# RS232_V2.net
KiCad netlist of a schematic drawn in Altium Designer
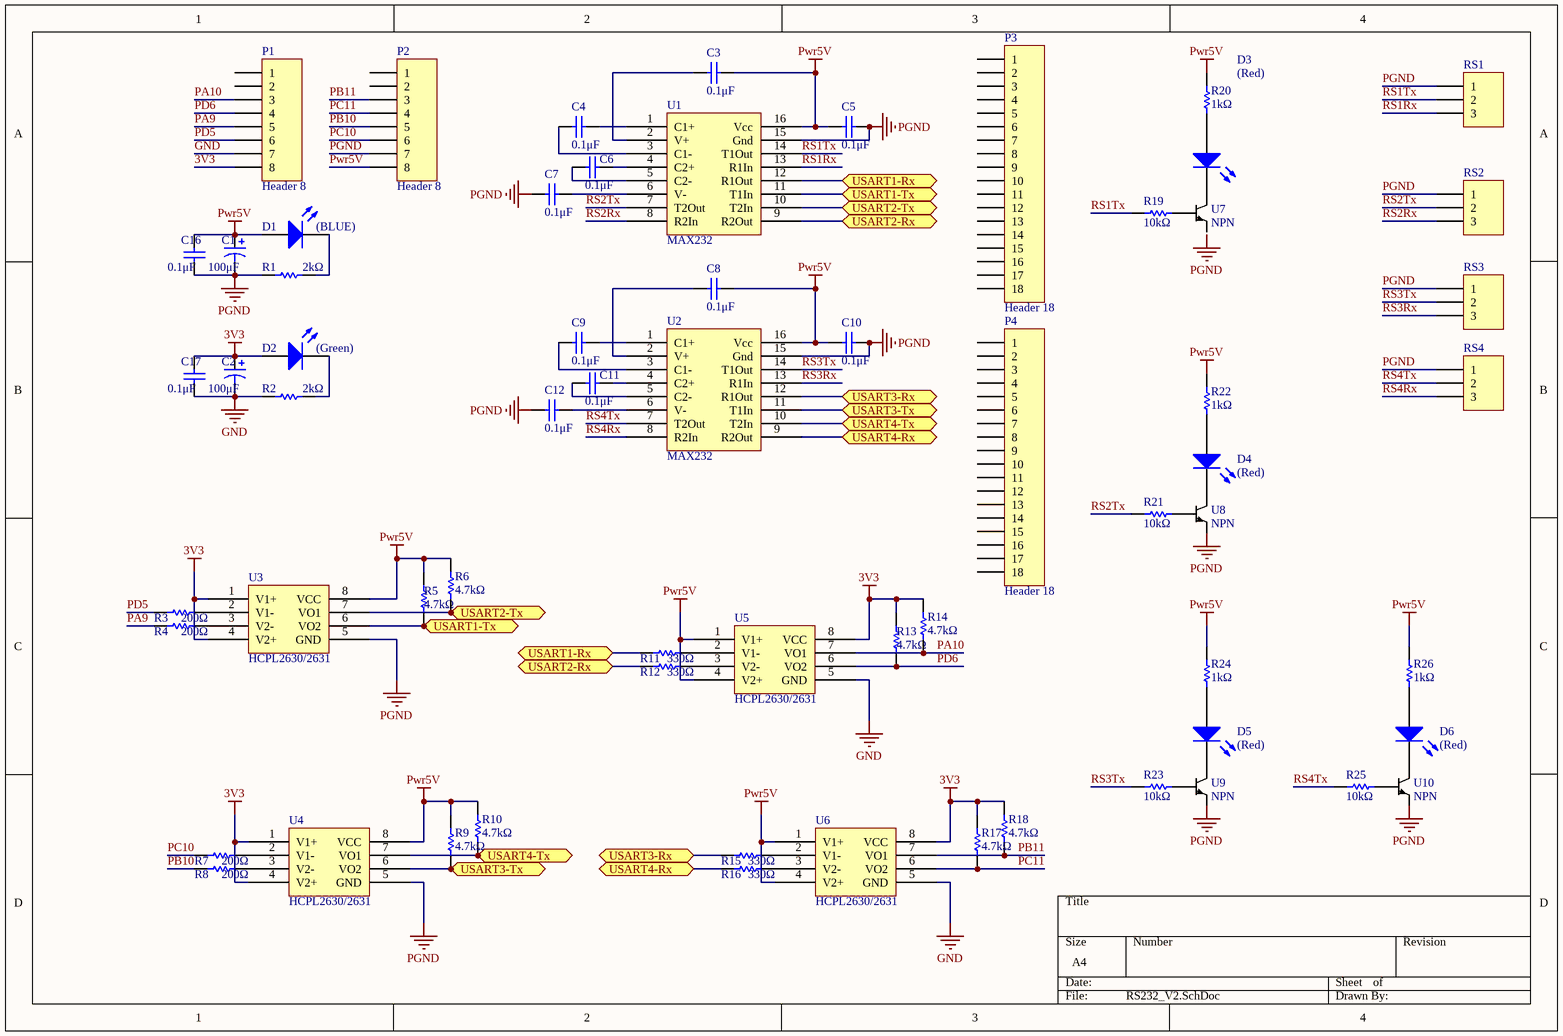
[diagram p0: RS232_V2.SchDoc]

(export (version "E")
  (design (tool "Eeschema 10.0.6"))
  (components
    (comp (ref "C1")
      (value "100μF")
      (footprint "CAP-TAN-6032/CAPC")
      (description "钽电容")
      (fields (field (name "Comment") "CAP-TAN") (field (name "PUBLISHER") "Altium Limited"))
      (libsource (lib "Libraries_2014_0215") (part "CAP-TAN"))
    )
    (comp (ref "C2")
      (value "100μF")
      (footprint "CAP-TAN-6032/CAPC")
      (description "钽电容")
      (fields (field (name "Comment") "CAP-TAN") (field (name "PUBLISHER") "Altium Limited"))
      (libsource (lib "Libraries_2014_0215") (part "CAP-TAN"))
    )
    (comp (ref "C3")
      (value "0.1μF")
      (footprint "CAP-MLCC-0603")
      (description "无极性电容")
      (fields (field (name "PUBLISHER") "Altium Limited"))
      (libsource (lib "Libraries_2014_0618") (part "CAP"))
    )
    (comp (ref "C4")
      (value "0.1μF")
      (footprint "CAP-MLCC-0603")
      (description "无极性电容")
      (fields (field (name "PUBLISHER") "Altium Limited"))
      (libsource (lib "Libraries_2014_0618") (part "CAP"))
    )
    (comp (ref "C5")
      (value "0.1μF")
      (footprint "CAP-MLCC-0603")
      (description "无极性电容")
      (fields (field (name "PUBLISHER") "Altium Limited"))
      (libsource (lib "Libraries_2014_0618") (part "CAP"))
    )
    (comp (ref "C6")
      (value "0.1μF")
      (footprint "CAP-MLCC-0603")
      (description "无极性电容")
      (fields (field (name "PUBLISHER") "Altium Limited"))
      (libsource (lib "Libraries_2014_0618") (part "CAP"))
    )
    (comp (ref "C7")
      (value "0.1μF")
      (footprint "CAP-MLCC-0603")
      (description "无极性电容")
      (fields (field (name "PUBLISHER") "Altium Limited"))
      (libsource (lib "Libraries_2014_0618") (part "CAP"))
    )
    (comp (ref "C8")
      (value "0.1μF")
      (footprint "CAP-MLCC-0603")
      (description "无极性电容")
      (fields (field (name "PUBLISHER") "Altium Limited"))
      (libsource (lib "Libraries_2014_0618") (part "CAP"))
    )
    (comp (ref "C9")
      (value "0.1μF")
      (footprint "CAP-MLCC-0603")
      (description "无极性电容")
      (fields (field (name "PUBLISHER") "Altium Limited"))
      (libsource (lib "Libraries_2014_0618") (part "CAP"))
    )
    (comp (ref "C10")
      (value "0.1μF")
      (footprint "CAP-MLCC-0603")
      (description "无极性电容")
      (fields (field (name "PUBLISHER") "Altium Limited"))
      (libsource (lib "Libraries_2014_0618") (part "CAP"))
    )
    (comp (ref "C11")
      (value "0.1μF")
      (footprint "CAP-MLCC-0603")
      (description "无极性电容")
      (fields (field (name "PUBLISHER") "Altium Limited"))
      (libsource (lib "Libraries_2014_0618") (part "CAP"))
    )
    (comp (ref "C12")
      (value "0.1μF")
      (footprint "CAP-MLCC-0603")
      (description "无极性电容")
      (fields (field (name "PUBLISHER") "Altium Limited"))
      (libsource (lib "Libraries_2014_0618") (part "CAP"))
    )
    (comp (ref "C16")
      (value "0.1μF")
      (footprint "CAP-MLCC-0603")
      (description "无极性电容")
      (fields (field (name "PUBLISHER") "Altium Limited"))
      (libsource (lib "Libraries_2014_0618") (part "CAP"))
    )
    (comp (ref "C17")
      (value "0.1μF")
      (footprint "CAP-MLCC-0603")
      (description "无极性电容")
      (fields (field (name "PUBLISHER") "Altium Limited"))
      (libsource (lib "Libraries_2014_0618") (part "CAP"))
    )
    (comp (ref "D1")
      (value "(BLUE)")
      (footprint "LED-0805")
      (description "LED")
      (fields (field (name "PUBLISHER") "Altium Limited"))
      (libsource (lib "Libraries_2014_0215") (part "LED"))
    )
    (comp (ref "D2")
      (value "(Green)")
      (footprint "LED-0805")
      (description "LED")
      (fields (field (name "PUBLISHER") "Altium Limited"))
      (libsource (lib "Libraries_2014_0215") (part "LED"))
    )
    (comp (ref "D3")
      (value "(Red)")
      (footprint "LED-0805")
      (description "LED")
      (fields (field (name "PUBLISHER") "Altium Limited"))
      (libsource (lib "Libraries_2014_0618") (part "LED"))
    )
    (comp (ref "D4")
      (value "(Red)")
      (footprint "LED-0805")
      (description "LED")
      (fields (field (name "PUBLISHER") "Altium Limited"))
      (libsource (lib "Libraries_2014_0618") (part "LED"))
    )
    (comp (ref "D5")
      (value "(Red)")
      (footprint "LED-0805")
      (description "LED")
      (fields (field (name "PUBLISHER") "Altium Limited"))
      (libsource (lib "Libraries_2014_0618") (part "LED"))
    )
    (comp (ref "D6")
      (value "(Red)")
      (footprint "LED-0805")
      (description "LED")
      (fields (field (name "PUBLISHER") "Altium Limited"))
      (libsource (lib "Libraries_2014_0618") (part "LED"))
    )
    (comp (ref "P1")
      (value "Header 8")
      (footprint "SIP8")
      (description "Header, 8-Pin")
      (fields (field (name "PUBLISHER") "Altium Limited"))
      (libsource (lib "Libraries_2014_0618") (part "Header 8"))
    )
    (comp (ref "P2")
      (value "Header 8")
      (footprint "SIP8")
      (description "Header, 8-Pin")
      (fields (field (name "PUBLISHER") "Altium Limited"))
      (libsource (lib "Libraries_2014_0618") (part "Header 8"))
    )
    (comp (ref "P3")
      (value "Header 18")
      (footprint "SIP18")
      (description "Header, 18-Pin")
      (fields (field (name "PUBLISHER") "Altium Limited"))
      (libsource (lib "Libraries_2014_0618") (part "Header 18"))
    )
    (comp (ref "P4")
      (value "Header 18")
      (footprint "SIP18")
      (description "Header, 18-Pin")
      (fields (field (name "PUBLISHER") "Altium Limited"))
      (libsource (lib "Libraries_2014_0618") (part "Header 18"))
    )
    (comp (ref "R1")
      (value "2kΩ")
      (footprint "RES-0603")
      (description "电阻")
      (fields (field (name "Comment") "RES") (field (name "PUBLISHER") "Altium Limited"))
      (libsource (lib "Libraries_2014_0215") (part "RES"))
    )
    (comp (ref "R2")
      (value "2kΩ")
      (footprint "RES-0603")
      (description "电阻")
      (fields (field (name "Comment") "RES") (field (name "PUBLISHER") "Altium Limited"))
      (libsource (lib "Libraries_2014_0215") (part "RES"))
    )
    (comp (ref "R3")
      (value "200Ω")
      (footprint "RES-0603")
      (description "电阻")
      (fields (field (name "PUBLISHER") "Altium Limited"))
      (libsource (lib "Libraries_2014_0618") (part "RES"))
    )
    (comp (ref "R4")
      (value "200Ω")
      (footprint "RES-0603")
      (description "电阻")
      (fields (field (name "PUBLISHER") "Altium Limited"))
      (libsource (lib "Libraries_2014_0618") (part "RES"))
    )
    (comp (ref "R5")
      (value "4.7kΩ")
      (footprint "RES-0603")
      (description "电阻")
      (fields (field (name "PUBLISHER") "Altium Limited"))
      (libsource (lib "Libraries_2014_0618") (part "RES"))
    )
    (comp (ref "R6")
      (value "4.7kΩ")
      (footprint "RES-0603")
      (description "电阻")
      (fields (field (name "PUBLISHER") "Altium Limited"))
      (libsource (lib "Libraries_2014_0618") (part "RES"))
    )
    (comp (ref "R7")
      (value "200Ω")
      (footprint "RES-0603")
      (description "电阻")
      (fields (field (name "PUBLISHER") "Altium Limited"))
      (libsource (lib "Libraries_2014_0618") (part "RES"))
    )
    (comp (ref "R8")
      (value "200Ω")
      (footprint "RES-0603")
      (description "电阻")
      (fields (field (name "PUBLISHER") "Altium Limited"))
      (libsource (lib "Libraries_2014_0618") (part "RES"))
    )
    (comp (ref "R9")
      (value "4.7kΩ")
      (footprint "RES-0603")
      (description "电阻")
      (fields (field (name "PUBLISHER") "Altium Limited"))
      (libsource (lib "Libraries_2014_0618") (part "RES"))
    )
    (comp (ref "R10")
      (value "4.7kΩ")
      (footprint "RES-0603")
      (description "电阻")
      (fields (field (name "PUBLISHER") "Altium Limited"))
      (libsource (lib "Libraries_2014_0618") (part "RES"))
    )
    (comp (ref "R11")
      (value "330Ω")
      (footprint "RES-0603")
      (description "电阻")
      (fields (field (name "PUBLISHER") "Altium Limited"))
      (libsource (lib "Libraries_2014_0618") (part "RES"))
    )
    (comp (ref "R12")
      (value "330Ω")
      (footprint "RES-0603")
      (description "电阻")
      (fields (field (name "PUBLISHER") "Altium Limited"))
      (libsource (lib "Libraries_2014_0618") (part "RES"))
    )
    (comp (ref "R13")
      (value "4.7kΩ")
      (footprint "RES-0603")
      (description "电阻")
      (fields (field (name "PUBLISHER") "Altium Limited"))
      (libsource (lib "Libraries_2014_0618") (part "RES"))
    )
    (comp (ref "R14")
      (value "4.7kΩ")
      (footprint "RES-0603")
      (description "电阻")
      (fields (field (name "PUBLISHER") "Altium Limited"))
      (libsource (lib "Libraries_2014_0618") (part "RES"))
    )
    (comp (ref "R15")
      (value "330Ω")
      (footprint "RES-0603")
      (description "电阻")
      (fields (field (name "PUBLISHER") "Altium Limited"))
      (libsource (lib "Libraries_2014_0618") (part "RES"))
    )
    (comp (ref "R16")
      (value "330Ω")
      (footprint "RES-0603")
      (description "电阻")
      (fields (field (name "PUBLISHER") "Altium Limited"))
      (libsource (lib "Libraries_2014_0618") (part "RES"))
    )
    (comp (ref "R17")
      (value "4.7kΩ")
      (footprint "RES-0603")
      (description "电阻")
      (fields (field (name "PUBLISHER") "Altium Limited"))
      (libsource (lib "Libraries_2014_0618") (part "RES"))
    )
    (comp (ref "R18")
      (value "4.7kΩ")
      (footprint "RES-0603")
      (description "电阻")
      (fields (field (name "PUBLISHER") "Altium Limited"))
      (libsource (lib "Libraries_2014_0618") (part "RES"))
    )
    (comp (ref "R19")
      (value "10kΩ")
      (footprint "RES-0603")
      (description "电阻")
      (fields (field (name "PUBLISHER") "Altium Limited"))
      (libsource (lib "Libraries_2014_0618") (part "RES"))
    )
    (comp (ref "R20")
      (value "1kΩ")
      (footprint "RES-0603")
      (description "电阻")
      (fields (field (name "PUBLISHER") "Altium Limited"))
      (libsource (lib "Libraries_2014_0618") (part "RES"))
    )
    (comp (ref "R21")
      (value "10kΩ")
      (footprint "RES-0603")
      (description "电阻")
      (fields (field (name "PUBLISHER") "Altium Limited"))
      (libsource (lib "Libraries_2014_0618") (part "RES"))
    )
    (comp (ref "R22")
      (value "1kΩ")
      (footprint "RES-0603")
      (description "电阻")
      (fields (field (name "PUBLISHER") "Altium Limited"))
      (libsource (lib "Libraries_2014_0618") (part "RES"))
    )
    (comp (ref "R23")
      (value "10kΩ")
      (footprint "RES-0603")
      (description "电阻")
      (fields (field (name "PUBLISHER") "Altium Limited"))
      (libsource (lib "Libraries_2014_0618") (part "RES"))
    )
    (comp (ref "R24")
      (value "1kΩ")
      (footprint "RES-0603")
      (description "电阻")
      (fields (field (name "PUBLISHER") "Altium Limited"))
      (libsource (lib "Libraries_2014_0618") (part "RES"))
    )
    (comp (ref "R25")
      (value "10kΩ")
      (footprint "RES-0603")
      (description "电阻")
      (fields (field (name "PUBLISHER") "Altium Limited"))
      (libsource (lib "Libraries_2014_0618") (part "RES"))
    )
    (comp (ref "R26")
      (value "1kΩ")
      (footprint "RES-0603")
      (description "电阻")
      (fields (field (name "PUBLISHER") "Altium Limited"))
      (libsource (lib "Libraries_2014_0618") (part "RES"))
    )
    (comp (ref "RS1")
      (value "Header 3")
      (footprint "Green_3P")
      (description "Header, 3-Pin")
      (fields (field (name "PUBLISHER") "Altium Limited"))
      (libsource (lib "Libraries_2014_0618") (part "Header 3"))
    )
    (comp (ref "RS2")
      (value "Header 3")
      (footprint "Green_3P")
      (description "Header, 3-Pin")
      (fields (field (name "PUBLISHER") "Altium Limited"))
      (libsource (lib "Libraries_2014_0618") (part "Header 3"))
    )
    (comp (ref "RS3")
      (value "Header 3")
      (footprint "Green_3P")
      (description "Header, 3-Pin")
      (fields (field (name "PUBLISHER") "Altium Limited"))
      (libsource (lib "Libraries_2014_0618") (part "Header 3"))
    )
    (comp (ref "RS4")
      (value "Header 3")
      (footprint "Green_3P")
      (description "Header, 3-Pin")
      (fields (field (name "PUBLISHER") "Altium Limited"))
      (libsource (lib "Libraries_2014_0618") (part "Header 3"))
    )
    (comp (ref "U1")
      (value "MAX232")
      (footprint "SOIC16")
      (libsource (lib "Libraries_2014_0618") (part "IC-MAX232"))
    )
    (comp (ref "U2")
      (value "MAX232")
      (footprint "SOIC16")
      (libsource (lib "Libraries_2014_0618") (part "IC-MAX232"))
    )
    (comp (ref "U3")
      (value "HCPL2630/2631")
      (footprint "SOP8")
      (libsource (lib "Libraries_2014_0618") (part "HCPL2630/2631"))
    )
    (comp (ref "U4")
      (value "HCPL2630/2631")
      (footprint "SOP8")
      (libsource (lib "Libraries_2014_0618") (part "HCPL2630/2631"))
    )
    (comp (ref "U5")
      (value "HCPL2630/2631")
      (footprint "SOP8")
      (libsource (lib "Libraries_2014_0618") (part "HCPL2630/2631"))
    )
    (comp (ref "U6")
      (value "HCPL2630/2631")
      (footprint "SOP8")
      (libsource (lib "Libraries_2014_0618") (part "HCPL2630/2631"))
    )
    (comp (ref "U7")
      (value "NPN")
      (footprint "SOT-23")
      (libsource (lib "Libraries_2014_0618") (part "NPN三极管"))
    )
    (comp (ref "U8")
      (value "NPN")
      (footprint "SOT-23")
      (libsource (lib "Libraries_2014_0618") (part "NPN三极管"))
    )
    (comp (ref "U9")
      (value "NPN")
      (footprint "SOT-23")
      (libsource (lib "Libraries_2014_0618") (part "NPN三极管"))
    )
    (comp (ref "U10")
      (value "NPN")
      (footprint "SOT-23")
      (libsource (lib "Libraries_2014_0618") (part "NPN三极管"))
    )
  )
  (nets
    (net (code "1") (name "/PA9") (class "Default")
      (node (ref "P1") (pin "5") (pinfunction "5_5") (pintype "passive"))
      (node (ref "R4") (pin "1") (pinfunction "1_1") (pintype "passive"))
    )
    (net (code "2") (name "/PA10") (class "Default")
      (node (ref "P1") (pin "3") (pinfunction "3_3") (pintype "passive"))
      (node (ref "R14") (pin "1") (pinfunction "1_1") (pintype "passive"))
      (node (ref "U5") (pin "7") (pinfunction "VO1_7") (pintype "power_in"))
    )
    (net (code "3") (name "/PB10") (class "Default")
      (node (ref "P2") (pin "5") (pinfunction "5_5") (pintype "passive"))
      (node (ref "R8") (pin "1") (pinfunction "1_1") (pintype "passive"))
    )
    (net (code "4") (name "/PB11") (class "Default")
      (node (ref "P2") (pin "3") (pinfunction "3_3") (pintype "passive"))
      (node (ref "R18") (pin "1") (pinfunction "1_1") (pintype "passive"))
      (node (ref "U6") (pin "7") (pinfunction "VO1_7") (pintype "power_in"))
    )
    (net (code "5") (name "/PC10") (class "Default")
      (node (ref "P2") (pin "6") (pinfunction "6_6") (pintype "passive"))
      (node (ref "R7") (pin "1") (pinfunction "1_1") (pintype "passive"))
    )
    (net (code "6") (name "/PC11") (class "Default")
      (node (ref "P2") (pin "4") (pinfunction "4_4") (pintype "passive"))
      (node (ref "R17") (pin "1") (pinfunction "1_1") (pintype "passive"))
      (node (ref "U6") (pin "6") (pinfunction "VO2_6") (pintype "power_in"))
    )
    (net (code "7") (name "/PD5") (class "Default")
      (node (ref "P1") (pin "6") (pinfunction "6_6") (pintype "passive"))
      (node (ref "R3") (pin "1") (pinfunction "1_1") (pintype "passive"))
    )
    (net (code "8") (name "/PD6") (class "Default")
      (node (ref "P1") (pin "4") (pinfunction "4_4") (pintype "passive"))
      (node (ref "R13") (pin "1") (pinfunction "1_1") (pintype "passive"))
      (node (ref "U5") (pin "6") (pinfunction "VO2_6") (pintype "power_in"))
    )
    (net (code "9") (name "/RS1Rx") (class "Default")
      (node (ref "RS1") (pin "3") (pinfunction "3_3") (pintype "passive"))
      (node (ref "U1") (pin "13") (pinfunction "R1In_13") (pintype "power_in"))
    )
    (net (code "10") (name "/RS1Tx") (class "Default")
      (node (ref "R19") (pin "1") (pinfunction "1_1") (pintype "passive"))
      (node (ref "RS1") (pin "2") (pinfunction "2_2") (pintype "passive"))
      (node (ref "U1") (pin "14") (pinfunction "T1Out_14") (pintype "power_in"))
    )
    (net (code "11") (name "/RS2Rx") (class "Default")
      (node (ref "RS2") (pin "3") (pinfunction "3_3") (pintype "passive"))
      (node (ref "U1") (pin "8") (pinfunction "R2In_8") (pintype "power_in"))
    )
    (net (code "12") (name "/RS2Tx") (class "Default")
      (node (ref "R21") (pin "1") (pinfunction "1_1") (pintype "passive"))
      (node (ref "RS2") (pin "2") (pinfunction "2_2") (pintype "passive"))
      (node (ref "U1") (pin "7") (pinfunction "T2Out_7") (pintype "power_in"))
    )
    (net (code "13") (name "/RS3Rx") (class "Default")
      (node (ref "RS3") (pin "3") (pinfunction "3_3") (pintype "passive"))
      (node (ref "U2") (pin "13") (pinfunction "R1In_13") (pintype "power_in"))
    )
    (net (code "14") (name "/RS3Tx") (class "Default")
      (node (ref "R23") (pin "1") (pinfunction "1_1") (pintype "passive"))
      (node (ref "RS3") (pin "2") (pinfunction "2_2") (pintype "passive"))
      (node (ref "U2") (pin "14") (pinfunction "T1Out_14") (pintype "power_in"))
    )
    (net (code "15") (name "/RS4Rx") (class "Default")
      (node (ref "RS4") (pin "3") (pinfunction "3_3") (pintype "passive"))
      (node (ref "U2") (pin "8") (pinfunction "R2In_8") (pintype "power_in"))
    )
    (net (code "16") (name "/RS4Tx") (class "Default")
      (node (ref "R25") (pin "1") (pinfunction "1_1") (pintype "passive"))
      (node (ref "RS4") (pin "2") (pinfunction "2_2") (pintype "passive"))
      (node (ref "U2") (pin "7") (pinfunction "T2Out_7") (pintype "power_in"))
    )
    (net (code "17") (name "/USART1-Rx") (class "Default")
      (node (ref "R11") (pin "1") (pinfunction "1_1") (pintype "passive"))
      (node (ref "U1") (pin "12") (pinfunction "R1Out_12") (pintype "power_in"))
    )
    (net (code "18") (name "/USART1-Tx") (class "Default")
      (node (ref "R5") (pin "1") (pinfunction "1_1") (pintype "passive"))
      (node (ref "U1") (pin "11") (pinfunction "T1In_11") (pintype "power_in"))
      (node (ref "U3") (pin "6") (pinfunction "VO2_6") (pintype "power_in"))
    )
    (net (code "19") (name "/USART2-Rx") (class "Default")
      (node (ref "R12") (pin "1") (pinfunction "1_1") (pintype "passive"))
      (node (ref "U1") (pin "9") (pinfunction "R2Out_9") (pintype "power_in"))
    )
    (net (code "20") (name "/USART2-Tx") (class "Default")
      (node (ref "R6") (pin "1") (pinfunction "1_1") (pintype "passive"))
      (node (ref "U1") (pin "10") (pinfunction "T2In_10") (pintype "power_in"))
      (node (ref "U3") (pin "7") (pinfunction "VO1_7") (pintype "power_in"))
    )
    (net (code "21") (name "/USART3-Rx") (class "Default")
      (node (ref "R15") (pin "1") (pinfunction "1_1") (pintype "passive"))
      (node (ref "U2") (pin "12") (pinfunction "R1Out_12") (pintype "power_in"))
    )
    (net (code "22") (name "/USART3-Tx") (class "Default")
      (node (ref "R9") (pin "1") (pinfunction "1_1") (pintype "passive"))
      (node (ref "U2") (pin "11") (pinfunction "T1In_11") (pintype "power_in"))
      (node (ref "U4") (pin "6") (pinfunction "VO2_6") (pintype "power_in"))
    )
    (net (code "23") (name "/USART4-Rx") (class "Default")
      (node (ref "R16") (pin "1") (pinfunction "1_1") (pintype "passive"))
      (node (ref "U2") (pin "9") (pinfunction "R2Out_9") (pintype "power_in"))
    )
    (net (code "24") (name "/USART4-Tx") (class "Default")
      (node (ref "R10") (pin "1") (pinfunction "1_1") (pintype "passive"))
      (node (ref "U2") (pin "10") (pinfunction "T2In_10") (pintype "power_in"))
      (node (ref "U4") (pin "7") (pinfunction "VO1_7") (pintype "power_in"))
    )
    (net (code "25") (name "3V3") (class "Default")
      (node (ref "C17") (pin "1") (pinfunction "1_1") (pintype "passive"))
      (node (ref "C2") (pin "1") (pinfunction "1_1") (pintype "passive"))
      (node (ref "D2") (pin "1") (pinfunction "A_1") (pintype "passive"))
      (node (ref "P1") (pin "8") (pinfunction "8_8") (pintype "passive"))
      (node (ref "R13") (pin "2") (pinfunction "2_2") (pintype "passive"))
      (node (ref "R14") (pin "2") (pinfunction "2_2") (pintype "passive"))
      (node (ref "R17") (pin "2") (pinfunction "2_2") (pintype "passive"))
      (node (ref "R18") (pin "2") (pinfunction "2_2") (pintype "passive"))
      (node (ref "U3") (pin "1") (pinfunction "V1+_1") (pintype "power_in"))
      (node (ref "U3") (pin "4") (pinfunction "V2+_4") (pintype "power_in"))
      (node (ref "U4") (pin "1") (pinfunction "V1+_1") (pintype "power_in"))
      (node (ref "U4") (pin "4") (pinfunction "V2+_4") (pintype "power_in"))
      (node (ref "U5") (pin "8") (pinfunction "VCC_8") (pintype "power_in"))
      (node (ref "U6") (pin "8") (pinfunction "VCC_8") (pintype "power_in"))
    )
    (net (code "26") (name "GND") (class "Default")
      (node (ref "C17") (pin "2") (pinfunction "2_2") (pintype "passive"))
      (node (ref "C2") (pin "2") (pinfunction "2_2") (pintype "passive"))
      (node (ref "P1") (pin "7") (pinfunction "7_7") (pintype "passive"))
      (node (ref "R2") (pin "1") (pinfunction "1_1") (pintype "passive"))
      (node (ref "U5") (pin "5") (pinfunction "GND_5") (pintype "power_in"))
      (node (ref "U6") (pin "5") (pinfunction "GND_5") (pintype "power_in"))
    )
    (net (code "27") (name "Net-(D1-K)") (class "Default")
      (node (ref "D1") (pin "2") (pinfunction "K_2") (pintype "passive"))
      (node (ref "R1") (pin "2") (pinfunction "2_2") (pintype "passive"))
    )
    (net (code "28") (name "Net-(D2-K)") (class "Default")
      (node (ref "D2") (pin "2") (pinfunction "K_2") (pintype "passive"))
      (node (ref "R2") (pin "2") (pinfunction "2_2") (pintype "passive"))
    )
    (net (code "29") (name "Net-(D3-A)") (class "Default")
      (node (ref "D3") (pin "1") (pinfunction "A_1") (pintype "passive"))
      (node (ref "R20") (pin "1") (pinfunction "1_1") (pintype "passive"))
    )
    (net (code "30") (name "Net-(D3-K)") (class "Default")
      (node (ref "D3") (pin "2") (pinfunction "K_2") (pintype "passive"))
      (node (ref "U7") (pin "3") (pinfunction "C_3") (pintype "passive"))
    )
    (net (code "31") (name "Net-(D4-A)") (class "Default")
      (node (ref "D4") (pin "1") (pinfunction "A_1") (pintype "passive"))
      (node (ref "R22") (pin "1") (pinfunction "1_1") (pintype "passive"))
    )
    (net (code "32") (name "Net-(D4-K)") (class "Default")
      (node (ref "D4") (pin "2") (pinfunction "K_2") (pintype "passive"))
      (node (ref "U8") (pin "3") (pinfunction "C_3") (pintype "passive"))
    )
    (net (code "33") (name "Net-(D5-A)") (class "Default")
      (node (ref "D5") (pin "1") (pinfunction "A_1") (pintype "passive"))
      (node (ref "R24") (pin "1") (pinfunction "1_1") (pintype "passive"))
    )
    (net (code "34") (name "Net-(D5-K)") (class "Default")
      (node (ref "D5") (pin "2") (pinfunction "K_2") (pintype "passive"))
      (node (ref "U9") (pin "3") (pinfunction "C_3") (pintype "passive"))
    )
    (net (code "35") (name "Net-(D6-A)") (class "Default")
      (node (ref "D6") (pin "1") (pinfunction "A_1") (pintype "passive"))
      (node (ref "R26") (pin "1") (pinfunction "1_1") (pintype "passive"))
    )
    (net (code "36") (name "Net-(D6-K)") (class "Default")
      (node (ref "D6") (pin "2") (pinfunction "K_2") (pintype "passive"))
      (node (ref "U10") (pin "3") (pinfunction "C_3") (pintype "passive"))
    )
    (net (code "37") (name "Net-(U1-C1+)") (class "Default")
      (node (ref "C4") (pin "2") (pinfunction "2_2") (pintype "passive"))
      (node (ref "U1") (pin "1") (pinfunction "C1+_1") (pintype "power_in"))
    )
    (net (code "38") (name "Net-(U1-C1-)") (class "Default")
      (node (ref "C4") (pin "1") (pinfunction "1_1") (pintype "passive"))
      (node (ref "U1") (pin "3") (pinfunction "C1-_3") (pintype "power_in"))
    )
    (net (code "39") (name "Net-(U1-C2+)") (class "Default")
      (node (ref "C6") (pin "2") (pinfunction "2_2") (pintype "passive"))
      (node (ref "U1") (pin "4") (pinfunction "C2+_4") (pintype "power_in"))
    )
    (net (code "40") (name "Net-(U1-C2-)") (class "Default")
      (node (ref "C6") (pin "1") (pinfunction "1_1") (pintype "passive"))
      (node (ref "U1") (pin "5") (pinfunction "C2-_5") (pintype "power_in"))
    )
    (net (code "41") (name "Net-(U1-V+)") (class "Default")
      (node (ref "C3") (pin "1") (pinfunction "1_1") (pintype "passive"))
      (node (ref "U1") (pin "2") (pinfunction "V+_2") (pintype "power_in"))
    )
    (net (code "42") (name "Net-(U1-V-)") (class "Default")
      (node (ref "C7") (pin "2") (pinfunction "2_2") (pintype "passive"))
      (node (ref "U1") (pin "6") (pinfunction "V-_6") (pintype "power_in"))
    )
    (net (code "43") (name "Net-(U2-C1+)") (class "Default")
      (node (ref "C9") (pin "2") (pinfunction "2_2") (pintype "passive"))
      (node (ref "U2") (pin "1") (pinfunction "C1+_1") (pintype "power_in"))
    )
    (net (code "44") (name "Net-(U2-C1-)") (class "Default")
      (node (ref "C9") (pin "1") (pinfunction "1_1") (pintype "passive"))
      (node (ref "U2") (pin "3") (pinfunction "C1-_3") (pintype "power_in"))
    )
    (net (code "45") (name "Net-(U2-C2+)") (class "Default")
      (node (ref "C11") (pin "2") (pinfunction "2_2") (pintype "passive"))
      (node (ref "U2") (pin "4") (pinfunction "C2+_4") (pintype "power_in"))
    )
    (net (code "46") (name "Net-(U2-C2-)") (class "Default")
      (node (ref "C11") (pin "1") (pinfunction "1_1") (pintype "passive"))
      (node (ref "U2") (pin "5") (pinfunction "C2-_5") (pintype "power_in"))
    )
    (net (code "47") (name "Net-(U2-V+)") (class "Default")
      (node (ref "C8") (pin "1") (pinfunction "1_1") (pintype "passive"))
      (node (ref "U2") (pin "2") (pinfunction "V+_2") (pintype "power_in"))
    )
    (net (code "48") (name "Net-(U2-V-)") (class "Default")
      (node (ref "C12") (pin "2") (pinfunction "2_2") (pintype "passive"))
      (node (ref "U2") (pin "6") (pinfunction "V-_6") (pintype "power_in"))
    )
    (net (code "49") (name "Net-(U3-V1-)") (class "Default")
      (node (ref "R3") (pin "2") (pinfunction "2_2") (pintype "passive"))
      (node (ref "U3") (pin "2") (pinfunction "V1-_2") (pintype "power_in"))
    )
    (net (code "50") (name "Net-(U3-V2-)") (class "Default")
      (node (ref "R4") (pin "2") (pinfunction "2_2") (pintype "passive"))
      (node (ref "U3") (pin "3") (pinfunction "V2-_3") (pintype "power_in"))
    )
    (net (code "51") (name "Net-(U4-V1-)") (class "Default")
      (node (ref "R7") (pin "2") (pinfunction "2_2") (pintype "passive"))
      (node (ref "U4") (pin "2") (pinfunction "V1-_2") (pintype "power_in"))
    )
    (net (code "52") (name "Net-(U4-V2-)") (class "Default")
      (node (ref "R8") (pin "2") (pinfunction "2_2") (pintype "passive"))
      (node (ref "U4") (pin "3") (pinfunction "V2-_3") (pintype "power_in"))
    )
    (net (code "53") (name "Net-(U5-V1-)") (class "Default")
      (node (ref "R11") (pin "2") (pinfunction "2_2") (pintype "passive"))
      (node (ref "U5") (pin "2") (pinfunction "V1-_2") (pintype "power_in"))
    )
    (net (code "54") (name "Net-(U5-V2-)") (class "Default")
      (node (ref "R12") (pin "2") (pinfunction "2_2") (pintype "passive"))
      (node (ref "U5") (pin "3") (pinfunction "V2-_3") (pintype "power_in"))
    )
    (net (code "55") (name "Net-(U6-V1-)") (class "Default")
      (node (ref "R15") (pin "2") (pinfunction "2_2") (pintype "passive"))
      (node (ref "U6") (pin "2") (pinfunction "V1-_2") (pintype "power_in"))
    )
    (net (code "56") (name "Net-(U6-V2-)") (class "Default")
      (node (ref "R16") (pin "2") (pinfunction "2_2") (pintype "passive"))
      (node (ref "U6") (pin "3") (pinfunction "V2-_3") (pintype "power_in"))
    )
    (net (code "57") (name "Net-(U7-B)") (class "Default")
      (node (ref "R19") (pin "2") (pinfunction "2_2") (pintype "passive"))
      (node (ref "U7") (pin "1") (pinfunction "B_1") (pintype "passive"))
    )
    (net (code "58") (name "Net-(U8-B)") (class "Default")
      (node (ref "R21") (pin "2") (pinfunction "2_2") (pintype "passive"))
      (node (ref "U8") (pin "1") (pinfunction "B_1") (pintype "passive"))
    )
    (net (code "59") (name "Net-(U9-B)") (class "Default")
      (node (ref "R23") (pin "2") (pinfunction "2_2") (pintype "passive"))
      (node (ref "U9") (pin "1") (pinfunction "B_1") (pintype "passive"))
    )
    (net (code "60") (name "Net-(U10-B)") (class "Default")
      (node (ref "R25") (pin "2") (pinfunction "2_2") (pintype "passive"))
      (node (ref "U10") (pin "1") (pinfunction "B_1") (pintype "passive"))
    )
    (net (code "61") (name "PGND") (class "Default")
      (node (ref "C1") (pin "2") (pinfunction "2_2") (pintype "passive"))
      (node (ref "C10") (pin "2") (pinfunction "2_2") (pintype "passive"))
      (node (ref "C12") (pin "1") (pinfunction "1_1") (pintype "passive"))
      (node (ref "C16") (pin "1") (pinfunction "1_1") (pintype "passive"))
      (node (ref "C5") (pin "2") (pinfunction "2_2") (pintype "passive"))
      (node (ref "C7") (pin "1") (pinfunction "1_1") (pintype "passive"))
      (node (ref "P2") (pin "7") (pinfunction "7_7") (pintype "passive"))
      (node (ref "R1") (pin "1") (pinfunction "1_1") (pintype "passive"))
      (node (ref "RS1") (pin "1") (pinfunction "1_1") (pintype "passive"))
      (node (ref "RS2") (pin "1") (pinfunction "1_1") (pintype "passive"))
      (node (ref "RS3") (pin "1") (pinfunction "1_1") (pintype "passive"))
      (node (ref "RS4") (pin "1") (pinfunction "1_1") (pintype "passive"))
      (node (ref "U1") (pin "15") (pinfunction "Gnd_15") (pintype "power_in"))
      (node (ref "U10") (pin "2") (pinfunction "E_2") (pintype "passive"))
      (node (ref "U2") (pin "15") (pinfunction "Gnd_15") (pintype "power_in"))
      (node (ref "U3") (pin "5") (pinfunction "GND_5") (pintype "power_in"))
      (node (ref "U4") (pin "5") (pinfunction "GND_5") (pintype "power_in"))
      (node (ref "U8") (pin "2") (pinfunction "E_2") (pintype "passive"))
      (node (ref "U9") (pin "2") (pinfunction "E_2") (pintype "passive"))
    )
    (net (code "62") (name "Pwr5V") (class "Default")
      (node (ref "C1") (pin "1") (pinfunction "1_1") (pintype "passive"))
      (node (ref "C10") (pin "1") (pinfunction "1_1") (pintype "passive"))
      (node (ref "C16") (pin "2") (pinfunction "2_2") (pintype "passive"))
      (node (ref "C3") (pin "2") (pinfunction "2_2") (pintype "passive"))
      (node (ref "C5") (pin "1") (pinfunction "1_1") (pintype "passive"))
      (node (ref "C8") (pin "2") (pinfunction "2_2") (pintype "passive"))
      (node (ref "D1") (pin "1") (pinfunction "A_1") (pintype "passive"))
      (node (ref "P2") (pin "8") (pinfunction "8_8") (pintype "passive"))
      (node (ref "R10") (pin "2") (pinfunction "2_2") (pintype "passive"))
      (node (ref "R20") (pin "2") (pinfunction "2_2") (pintype "passive"))
      (node (ref "R22") (pin "2") (pinfunction "2_2") (pintype "passive"))
      (node (ref "R24") (pin "2") (pinfunction "2_2") (pintype "passive"))
      (node (ref "R26") (pin "2") (pinfunction "2_2") (pintype "passive"))
      (node (ref "R5") (pin "2") (pinfunction "2_2") (pintype "passive"))
      (node (ref "R6") (pin "2") (pinfunction "2_2") (pintype "passive"))
      (node (ref "R9") (pin "2") (pinfunction "2_2") (pintype "passive"))
      (node (ref "U1") (pin "16") (pinfunction "Vcc_16") (pintype "power_in"))
      (node (ref "U2") (pin "16") (pinfunction "Vcc_16") (pintype "power_in"))
      (node (ref "U3") (pin "8") (pinfunction "VCC_8") (pintype "power_in"))
      (node (ref "U4") (pin "8") (pinfunction "VCC_8") (pintype "power_in"))
      (node (ref "U5") (pin "1") (pinfunction "V1+_1") (pintype "power_in"))
      (node (ref "U5") (pin "4") (pinfunction "V2+_4") (pintype "power_in"))
      (node (ref "U6") (pin "1") (pinfunction "V1+_1") (pintype "power_in"))
      (node (ref "U6") (pin "4") (pinfunction "V2+_4") (pintype "power_in"))
    )
    (net (code "63") (name "unconnected-(P1-Pad1)") (class "Default")
      (node (ref "P1") (pin "1") (pinfunction "1_1") (pintype "passive"))
    )
    (net (code "64") (name "unconnected-(P1-Pad2)") (class "Default")
      (node (ref "P1") (pin "2") (pinfunction "2_2") (pintype "passive"))
    )
    (net (code "65") (name "unconnected-(P2-Pad1)") (class "Default")
      (node (ref "P2") (pin "1") (pinfunction "1_1") (pintype "passive"))
    )
    (net (code "66") (name "unconnected-(P2-Pad2)") (class "Default")
      (node (ref "P2") (pin "2") (pinfunction "2_2") (pintype "passive"))
    )
    (net (code "67") (name "unconnected-(P3-Pad1)") (class "Default")
      (node (ref "P3") (pin "1") (pinfunction "1_1") (pintype "passive"))
    )
    (net (code "68") (name "unconnected-(P3-Pad2)") (class "Default")
      (node (ref "P3") (pin "2") (pinfunction "2_2") (pintype "passive"))
    )
    (net (code "69") (name "unconnected-(P3-Pad3)") (class "Default")
      (node (ref "P3") (pin "3") (pinfunction "3_3") (pintype "passive"))
    )
    (net (code "70") (name "unconnected-(P3-Pad4)") (class "Default")
      (node (ref "P3") (pin "4") (pinfunction "4_4") (pintype "passive"))
    )
    (net (code "71") (name "unconnected-(P3-Pad5)") (class "Default")
      (node (ref "P3") (pin "5") (pinfunction "5_5") (pintype "passive"))
    )
    (net (code "72") (name "unconnected-(P3-Pad6)") (class "Default")
      (node (ref "P3") (pin "6") (pinfunction "6_6") (pintype "passive"))
    )
    (net (code "73") (name "unconnected-(P3-Pad7)") (class "Default")
      (node (ref "P3") (pin "7") (pinfunction "7_7") (pintype "passive"))
    )
    (net (code "74") (name "unconnected-(P3-Pad8)") (class "Default")
      (node (ref "P3") (pin "8") (pinfunction "8_8") (pintype "passive"))
    )
    (net (code "75") (name "unconnected-(P3-Pad9)") (class "Default")
      (node (ref "P3") (pin "9") (pinfunction "9_9") (pintype "passive"))
    )
    (net (code "76") (name "unconnected-(P3-Pad10)") (class "Default")
      (node (ref "P3") (pin "10") (pinfunction "10_10") (pintype "passive"))
    )
    (net (code "77") (name "unconnected-(P3-Pad11)") (class "Default")
      (node (ref "P3") (pin "11") (pinfunction "11_11") (pintype "passive"))
    )
    (net (code "78") (name "unconnected-(P3-Pad12)") (class "Default")
      (node (ref "P3") (pin "12") (pinfunction "12_12") (pintype "passive"))
    )
    (net (code "79") (name "unconnected-(P3-Pad13)") (class "Default")
      (node (ref "P3") (pin "13") (pinfunction "13_13") (pintype "passive"))
    )
    (net (code "80") (name "unconnected-(P3-Pad14)") (class "Default")
      (node (ref "P3") (pin "14") (pinfunction "14_14") (pintype "passive"))
    )
    (net (code "81") (name "unconnected-(P3-Pad15)") (class "Default")
      (node (ref "P3") (pin "15") (pinfunction "15_15") (pintype "passive"))
    )
    (net (code "82") (name "unconnected-(P3-Pad16)") (class "Default")
      (node (ref "P3") (pin "16") (pinfunction "16_16") (pintype "passive"))
    )
    (net (code "83") (name "unconnected-(P3-Pad17)") (class "Default")
      (node (ref "P3") (pin "17") (pinfunction "17_17") (pintype "passive"))
    )
    (net (code "84") (name "unconnected-(P3-Pad18)") (class "Default")
      (node (ref "P3") (pin "18") (pinfunction "18_18") (pintype "passive"))
    )
    (net (code "85") (name "unconnected-(P4-Pad1)") (class "Default")
      (node (ref "P4") (pin "1") (pinfunction "1_1") (pintype "passive"))
    )
    (net (code "86") (name "unconnected-(P4-Pad2)") (class "Default")
      (node (ref "P4") (pin "2") (pinfunction "2_2") (pintype "passive"))
    )
    (net (code "87") (name "unconnected-(P4-Pad3)") (class "Default")
      (node (ref "P4") (pin "3") (pinfunction "3_3") (pintype "passive"))
    )
    (net (code "88") (name "unconnected-(P4-Pad4)") (class "Default")
      (node (ref "P4") (pin "4") (pinfunction "4_4") (pintype "passive"))
    )
    (net (code "89") (name "unconnected-(P4-Pad5)") (class "Default")
      (node (ref "P4") (pin "5") (pinfunction "5_5") (pintype "passive"))
    )
    (net (code "90") (name "unconnected-(P4-Pad6)") (class "Default")
      (node (ref "P4") (pin "6") (pinfunction "6_6") (pintype "passive"))
    )
    (net (code "91") (name "unconnected-(P4-Pad7)") (class "Default")
      (node (ref "P4") (pin "7") (pinfunction "7_7") (pintype "passive"))
    )
    (net (code "92") (name "unconnected-(P4-Pad8)") (class "Default")
      (node (ref "P4") (pin "8") (pinfunction "8_8") (pintype "passive"))
    )
    (net (code "93") (name "unconnected-(P4-Pad9)") (class "Default")
      (node (ref "P4") (pin "9") (pinfunction "9_9") (pintype "passive"))
    )
    (net (code "94") (name "unconnected-(P4-Pad10)") (class "Default")
      (node (ref "P4") (pin "10") (pinfunction "10_10") (pintype "passive"))
    )
    (net (code "95") (name "unconnected-(P4-Pad11)") (class "Default")
      (node (ref "P4") (pin "11") (pinfunction "11_11") (pintype "passive"))
    )
    (net (code "96") (name "unconnected-(P4-Pad12)") (class "Default")
      (node (ref "P4") (pin "12") (pinfunction "12_12") (pintype "passive"))
    )
    (net (code "97") (name "unconnected-(P4-Pad13)") (class "Default")
      (node (ref "P4") (pin "13") (pinfunction "13_13") (pintype "passive"))
    )
    (net (code "98") (name "unconnected-(P4-Pad14)") (class "Default")
      (node (ref "P4") (pin "14") (pinfunction "14_14") (pintype "passive"))
    )
    (net (code "99") (name "unconnected-(P4-Pad15)") (class "Default")
      (node (ref "P4") (pin "15") (pinfunction "15_15") (pintype "passive"))
    )
    (net (code "100") (name "unconnected-(P4-Pad16)") (class "Default")
      (node (ref "P4") (pin "16") (pinfunction "16_16") (pintype "passive"))
    )
    (net (code "101") (name "unconnected-(P4-Pad17)") (class "Default")
      (node (ref "P4") (pin "17") (pinfunction "17_17") (pintype "passive"))
    )
    (net (code "102") (name "unconnected-(P4-Pad18)") (class "Default")
      (node (ref "P4") (pin "18") (pinfunction "18_18") (pintype "passive"))
    )
    (net (code "103") (name "unconnected-(U7-E-Pad2)") (class "Default")
      (node (ref "U7") (pin "2") (pinfunction "E_2") (pintype "passive"))
    )
  )
)
